# distribution.net
KiCad netlist of a schematic drawn in EAGLE
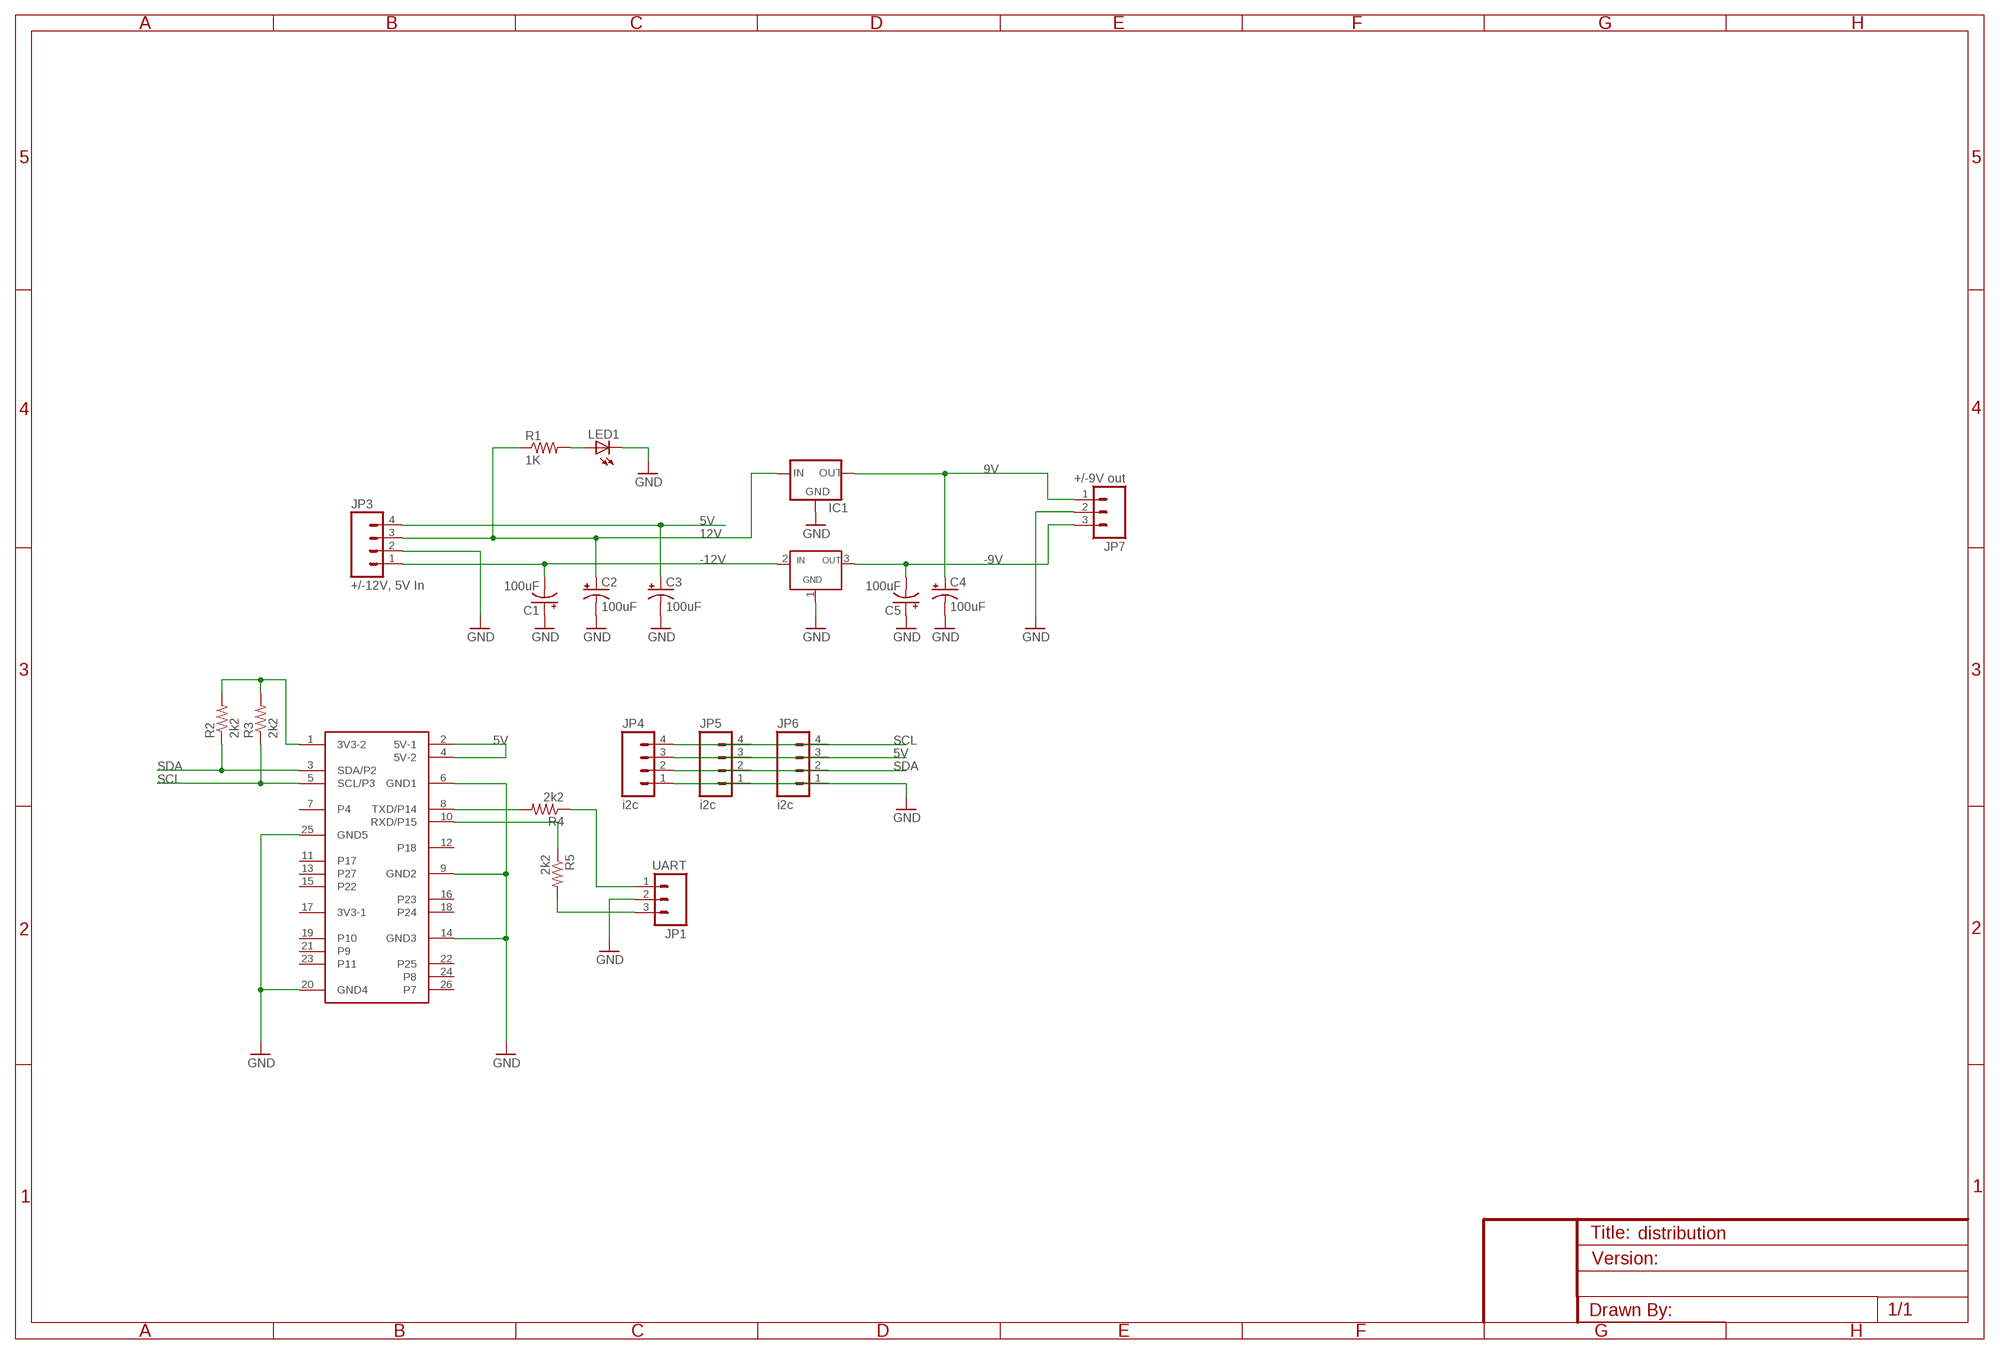
[diagram p0: schematic, sheet 1]

(export (version "E")
  (design (tool "Eeschema 10.0.6"))
  (components
    (comp (ref "C1")
      (value "100uF")
      (footprint "eagle-import:CPOL-RADIAL-100UF-25V")
      (libsource (lib "eagle-import") (part "CAP_POLPTH1"))
    )
    (comp (ref "C2")
      (value "100uF")
      (footprint "eagle-import:CPOL-RADIAL-100UF-25V")
      (libsource (lib "eagle-import") (part "CAP_POLPTH1"))
    )
    (comp (ref "C3")
      (value "100uF")
      (footprint "eagle-import:CPOL-RADIAL-100UF-25V")
      (libsource (lib "eagle-import") (part "CAP_POLPTH1"))
    )
    (comp (ref "C4")
      (value "100uF")
      (footprint "eagle-import:CPOL-RADIAL-100UF-25V")
      (libsource (lib "eagle-import") (part "CAP_POLPTH1"))
    )
    (comp (ref "C5")
      (value "100uF")
      (footprint "eagle-import:CPOL-RADIAL-100UF-25V")
      (libsource (lib "eagle-import") (part "CAP_POLPTH1"))
    )
    (comp (ref "IC1")
      (value "78XXS")
      (footprint "eagle-import:78XXS")
      (libsource (lib "eagle-import") (part "78XXS"))
    )
    (comp (ref "JP1")
      (value "UART")
      (footprint "eagle-import:MOLEX-1X3")
      (libsource (lib "eagle-import") (part "M03POLAR"))
    )
    (comp (ref "JP3")
      (value "+/-12V, 5V In")
      (footprint "eagle-import:SCREWTERMINAL-3.5MM-4")
      (libsource (lib "eagle-import") (part "M04SCREW"))
    )
    (comp (ref "JP4")
      (value "i2c")
      (footprint "eagle-import:MOLEX-1X4")
      (libsource (lib "eagle-import") (part "M04POLAR"))
    )
    (comp (ref "JP5")
      (value "i2c")
      (footprint "eagle-import:MOLEX-1X4")
      (libsource (lib "eagle-import") (part "M04POLAR"))
    )
    (comp (ref "JP6")
      (value "i2c")
      (footprint "eagle-import:MOLEX-1X4")
      (libsource (lib "eagle-import") (part "M04POLAR"))
    )
    (comp (ref "JP7")
      (value "+/-9V out")
      (footprint "eagle-import:MOLEX-1X3")
      (libsource (lib "eagle-import") (part "M03POLAR"))
    )
    (comp (ref "LED1")
      (value "LED1206")
      (footprint "eagle-import:LED-1206")
      (libsource (lib "eagle-import") (part "LED1206"))
    )
    (comp (ref "R1")
      (value "1K")
      (footprint "eagle-import:1206")
      (libsource (lib "eagle-import") (part "RESISTOR1206"))
    )
    (comp (ref "R2")
      (value "2k2")
      (footprint "eagle-import:1206")
      (libsource (lib "eagle-import") (part "RESISTOR1206"))
    )
    (comp (ref "R3")
      (value "2k2")
      (footprint "eagle-import:1206")
      (libsource (lib "eagle-import") (part "RESISTOR1206"))
    )
    (comp (ref "R4")
      (value "2k2")
      (footprint "eagle-import:1206")
      (libsource (lib "eagle-import") (part "RESISTOR1206"))
    )
    (comp (ref "R5")
      (value "2k2")
      (footprint "eagle-import:1206")
      (libsource (lib "eagle-import") (part "RESISTOR1206"))
    )
    (comp (ref "U$1")
      (value "VREG-GIO")
      (footprint "eagle-import:TO-220V")
      (libsource (lib "eagle-import") (part "VREG-GIO"))
    )
    (comp (ref "U$2")
      (value "PI-GPIO")
      (footprint "eagle-import:M2X13")
      (libsource (lib "eagle-import") (part "PI-GPIO"))
    )
  )
  (nets
    (net (code "1") (name "/-9V") (class "Default")
      (node (ref "C5") (pin "2") (pinfunction "-_2") (pintype "passive"))
      (node (ref "JP7") (pin "3") (pinfunction "3_3") (pintype "passive"))
      (node (ref "U$1") (pin "3") (pinfunction "OUT_3") (pintype "bidirectional"))
    )
    (net (code "2") (name "/-12V") (class "Default")
      (node (ref "C1") (pin "2") (pinfunction "-_2") (pintype "passive"))
      (node (ref "JP3") (pin "1") (pinfunction "1_1") (pintype "passive"))
      (node (ref "U$1") (pin "2") (pinfunction "IN_2") (pintype "bidirectional"))
    )
    (net (code "3") (name "/5V") (class "Default")
      (node (ref "C3") (pin "1") (pinfunction "+_1") (pintype "passive"))
      (node (ref "JP3") (pin "4") (pinfunction "4_4") (pintype "passive"))
      (node (ref "JP4") (pin "3") (pinfunction "3_3") (pintype "passive"))
      (node (ref "JP5") (pin "3") (pinfunction "3_3") (pintype "passive"))
      (node (ref "JP6") (pin "3") (pinfunction "3_3") (pintype "passive"))
      (node (ref "U$2") (pin "2") (pinfunction "5V-1_2") (pintype "bidirectional"))
      (node (ref "U$2") (pin "4") (pinfunction "5V-2_4") (pintype "bidirectional"))
    )
    (net (code "4") (name "/9V") (class "Default")
      (node (ref "C4") (pin "1") (pinfunction "+_1") (pintype "passive"))
      (node (ref "IC1") (pin "OUT") (pinfunction "OUT_OUT") (pintype "passive"))
      (node (ref "JP7") (pin "1") (pinfunction "1_1") (pintype "passive"))
    )
    (net (code "5") (name "/12V") (class "Default")
      (node (ref "C2") (pin "1") (pinfunction "+_1") (pintype "passive"))
      (node (ref "IC1") (pin "IN") (pinfunction "IN_IN") (pintype "input"))
      (node (ref "JP3") (pin "3") (pinfunction "3_3") (pintype "passive"))
      (node (ref "R1") (pin "1") (pinfunction "1_1") (pintype "passive"))
    )
    (net (code "6") (name "/SCL") (class "Default")
      (node (ref "JP4") (pin "4") (pinfunction "4_4") (pintype "passive"))
      (node (ref "JP5") (pin "4") (pinfunction "4_4") (pintype "passive"))
      (node (ref "JP6") (pin "4") (pinfunction "4_4") (pintype "passive"))
      (node (ref "R3") (pin "1") (pinfunction "1_1") (pintype "passive"))
      (node (ref "U$2") (pin "5") (pinfunction "SCL/P3_5") (pintype "bidirectional"))
    )
    (net (code "7") (name "/SDA") (class "Default")
      (node (ref "JP4") (pin "2") (pinfunction "2_2") (pintype "passive"))
      (node (ref "JP5") (pin "2") (pinfunction "2_2") (pintype "passive"))
      (node (ref "JP6") (pin "2") (pinfunction "2_2") (pintype "passive"))
      (node (ref "R2") (pin "1") (pinfunction "1_1") (pintype "passive"))
      (node (ref "U$2") (pin "3") (pinfunction "SDA/P2_3") (pintype "bidirectional"))
    )
    (net (code "8") (name "GND") (class "Default")
      (node (ref "C1") (pin "1") (pinfunction "+_1") (pintype "passive"))
      (node (ref "C2") (pin "2") (pinfunction "-_2") (pintype "passive"))
      (node (ref "C3") (pin "2") (pinfunction "-_2") (pintype "passive"))
      (node (ref "C4") (pin "2") (pinfunction "-_2") (pintype "passive"))
      (node (ref "C5") (pin "1") (pinfunction "+_1") (pintype "passive"))
      (node (ref "IC1") (pin "GND") (pinfunction "GND_GND") (pintype "input"))
      (node (ref "JP1") (pin "2") (pinfunction "2_2") (pintype "passive"))
      (node (ref "JP3") (pin "2") (pinfunction "2_2") (pintype "passive"))
      (node (ref "JP4") (pin "1") (pinfunction "1_1") (pintype "passive"))
      (node (ref "JP5") (pin "1") (pinfunction "1_1") (pintype "passive"))
      (node (ref "JP6") (pin "1") (pinfunction "1_1") (pintype "passive"))
      (node (ref "JP7") (pin "2") (pinfunction "2_2") (pintype "passive"))
      (node (ref "LED1") (pin "C") (pinfunction "C_C") (pintype "passive"))
      (node (ref "U$1") (pin "1") (pinfunction "GND_1") (pintype "bidirectional"))
      (node (ref "U$2") (pin "14") (pinfunction "GND3_14") (pintype "bidirectional"))
      (node (ref "U$2") (pin "20") (pinfunction "GND4_20") (pintype "bidirectional"))
      (node (ref "U$2") (pin "25") (pinfunction "GND5_25") (pintype "bidirectional"))
      (node (ref "U$2") (pin "6") (pinfunction "GND1_6") (pintype "bidirectional"))
      (node (ref "U$2") (pin "9") (pinfunction "GND2_9") (pintype "bidirectional"))
    )
    (net (code "9") (name "Net-(JP1-Pad1)") (class "Default")
      (node (ref "JP1") (pin "1") (pinfunction "1_1") (pintype "passive"))
      (node (ref "R4") (pin "1") (pinfunction "1_1") (pintype "passive"))
    )
    (net (code "10") (name "Net-(JP1-Pad3)") (class "Default")
      (node (ref "JP1") (pin "3") (pinfunction "3_3") (pintype "passive"))
      (node (ref "R5") (pin "2") (pinfunction "2_2") (pintype "passive"))
    )
    (net (code "11") (name "Net-(LED1-PadA)") (class "Default")
      (node (ref "LED1") (pin "A") (pinfunction "A_A") (pintype "passive"))
      (node (ref "R1") (pin "2") (pinfunction "2_2") (pintype "passive"))
    )
    (net (code "12") (name "Net-(U$2-3V3-2)") (class "Default")
      (node (ref "R2") (pin "2") (pinfunction "2_2") (pintype "passive"))
      (node (ref "R3") (pin "2") (pinfunction "2_2") (pintype "passive"))
      (node (ref "U$2") (pin "1") (pinfunction "3V3-2_1") (pintype "bidirectional"))
    )
    (net (code "13") (name "Net-(U$2-RXD{slash}P15)") (class "Default")
      (node (ref "R5") (pin "1") (pinfunction "1_1") (pintype "passive"))
      (node (ref "U$2") (pin "10") (pinfunction "RXD/P15_10") (pintype "bidirectional"))
    )
    (net (code "14") (name "Net-(U$2-TXD{slash}P14)") (class "Default")
      (node (ref "R4") (pin "2") (pinfunction "2_2") (pintype "passive"))
      (node (ref "U$2") (pin "8") (pinfunction "TXD/P14_8") (pintype "bidirectional"))
    )
    (net (code "15") (name "unconnected-(U$2-3V3-1-Pad17)") (class "Default")
      (node (ref "U$2") (pin "17") (pinfunction "3V3-1_17") (pintype "bidirectional"))
    )
    (net (code "16") (name "unconnected-(U$2-P4-Pad7)") (class "Default")
      (node (ref "U$2") (pin "7") (pinfunction "P4_7") (pintype "bidirectional"))
    )
    (net (code "17") (name "unconnected-(U$2-P7-Pad26)") (class "Default")
      (node (ref "U$2") (pin "26") (pinfunction "P7_26") (pintype "bidirectional"))
    )
    (net (code "18") (name "unconnected-(U$2-P8-Pad24)") (class "Default")
      (node (ref "U$2") (pin "24") (pinfunction "P8_24") (pintype "bidirectional"))
    )
    (net (code "19") (name "unconnected-(U$2-P9-Pad21)") (class "Default")
      (node (ref "U$2") (pin "21") (pinfunction "P9_21") (pintype "bidirectional"))
    )
    (net (code "20") (name "unconnected-(U$2-P10-Pad19)") (class "Default")
      (node (ref "U$2") (pin "19") (pinfunction "P10_19") (pintype "bidirectional"))
    )
    (net (code "21") (name "unconnected-(U$2-P11-Pad23)") (class "Default")
      (node (ref "U$2") (pin "23") (pinfunction "P11_23") (pintype "bidirectional"))
    )
    (net (code "22") (name "unconnected-(U$2-P17-Pad11)") (class "Default")
      (node (ref "U$2") (pin "11") (pinfunction "P17_11") (pintype "bidirectional"))
    )
    (net (code "23") (name "unconnected-(U$2-P18-Pad12)") (class "Default")
      (node (ref "U$2") (pin "12") (pinfunction "P18_12") (pintype "bidirectional"))
    )
    (net (code "24") (name "unconnected-(U$2-P22-Pad15)") (class "Default")
      (node (ref "U$2") (pin "15") (pinfunction "P22_15") (pintype "bidirectional"))
    )
    (net (code "25") (name "unconnected-(U$2-P23-Pad16)") (class "Default")
      (node (ref "U$2") (pin "16") (pinfunction "P23_16") (pintype "bidirectional"))
    )
    (net (code "26") (name "unconnected-(U$2-P24-Pad18)") (class "Default")
      (node (ref "U$2") (pin "18") (pinfunction "P24_18") (pintype "bidirectional"))
    )
    (net (code "27") (name "unconnected-(U$2-P25-Pad22)") (class "Default")
      (node (ref "U$2") (pin "22") (pinfunction "P25_22") (pintype "bidirectional"))
    )
    (net (code "28") (name "unconnected-(U$2-P27-Pad13)") (class "Default")
      (node (ref "U$2") (pin "13") (pinfunction "P27_13") (pintype "bidirectional"))
    )
  )
)
